# week7.net
KiCad netlist of a schematic drawn in EAGLE
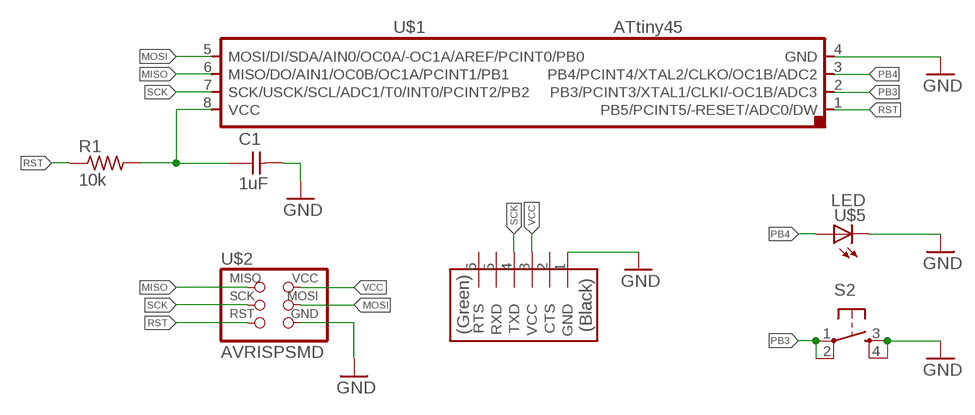
[diagram p0: schematic, sheet 1]

(export (version "E")
  (design (tool "Eeschema 10.0.6"))
  (components
    (comp (ref "C1")
      (value "1uF")
      (footprint "eagle-import:C1206FAB")
      (libsource (lib "eagle-import") (part "CAP-UNPOLARIZEDFAB"))
    )
    (comp (ref "R1")
      (value "10k")
      (footprint "eagle-import:R1206")
      (libsource (lib "eagle-import") (part "RES-US1206"))
    )
    (comp (ref "S2")
      (value "6MM_SWITCH6MM_SWITCH")
      (footprint "eagle-import:6MM_SWITCH")
      (libsource (lib "eagle-import") (part "6MM_SWITCH6MM_SWITCH"))
    )
    (comp (ref "U$1")
      (value "ATTINY45SI")
      (footprint "eagle-import:SOIC8")
      (libsource (lib "eagle-import") (part "ATTINY45SI"))
    )
    (comp (ref "U$2")
      (value "AVRISPSMD")
      (footprint "eagle-import:2X03SMD")
      (libsource (lib "eagle-import") (part "AVRISPSMD"))
    )
    (comp (ref "U$3")
      (value "FTDI-SMD-HEADER")
      (footprint "eagle-import:1X06SMD")
      (libsource (lib "eagle-import") (part "FTDI-SMD-HEADER"))
    )
    (comp (ref "U$5")
      (value "LED")
      (footprint "eagle-import:LED1206")
      (libsource (lib "eagle-import") (part "LED"))
    )
  )
  (nets
    (net (code "1") (name "GND") (class "Default")
      (node (ref "C1") (pin "2") (pinfunction "2_2") (pintype "passive"))
      (node (ref "S2") (pin "3") (pinfunction "S_3") (pintype "passive"))
      (node (ref "S2") (pin "4") (pinfunction "S1_4") (pintype "passive"))
      (node (ref "U$1") (pin "4") (pinfunction "GND_4") (pintype "bidirectional"))
      (node (ref "U$2") (pin "6") (pinfunction "GND_6") (pintype "passive"))
      (node (ref "U$3") (pin "1") (pinfunction "GND_1") (pintype "bidirectional"))
      (node (ref "U$5") (pin "2") (pinfunction "C_2") (pintype "passive"))
    )
    (net (code "2") (name "MISO") (class "Default")
      (node (ref "U$1") (pin "6") (pinfunction "MISO/DO/AIN1/OC0B/OC1A/PCINT1/PB1_6") (pintype "bidirectional"))
      (node (ref "U$2") (pin "1") (pinfunction "MISO_1") (pintype "passive"))
    )
    (net (code "3") (name "MOSI") (class "Default")
      (node (ref "U$1") (pin "5") (pinfunction "MOSI/DI/SDA/AIN0/OC0A/-OC1A/AREF/PCINT0/PB0_5") (pintype "bidirectional"))
      (node (ref "U$2") (pin "4") (pinfunction "MOSI_4") (pintype "passive"))
    )
    (net (code "4") (name "Net-(U$1-VCC)") (class "Default")
      (node (ref "C1") (pin "1") (pinfunction "1_1") (pintype "passive"))
      (node (ref "R1") (pin "2") (pinfunction "2_2") (pintype "passive"))
      (node (ref "U$1") (pin "8") (pinfunction "VCC_8") (pintype "bidirectional"))
    )
    (net (code "5") (name "PB3") (class "Default")
      (node (ref "S2") (pin "1") (pinfunction "P_1") (pintype "passive"))
      (node (ref "S2") (pin "2") (pinfunction "P1_2") (pintype "passive"))
      (node (ref "U$1") (pin "2") (pinfunction "PB3/PCINT3/XTAL1/CLKI/-OC1B/ADC3_2") (pintype "bidirectional"))
    )
    (net (code "6") (name "PB4") (class "Default")
      (node (ref "U$1") (pin "3") (pinfunction "PB4/PCINT4/XTAL2/CLKO/OC1B/ADC2_3") (pintype "bidirectional"))
      (node (ref "U$5") (pin "1") (pinfunction "A_1") (pintype "passive"))
    )
    (net (code "7") (name "RST") (class "Default")
      (node (ref "R1") (pin "1") (pinfunction "1_1") (pintype "passive"))
      (node (ref "U$1") (pin "1") (pinfunction "PB5/PCINT5/-RESET/ADC0/DW_1") (pintype "bidirectional"))
      (node (ref "U$2") (pin "5") (pinfunction "RST_5") (pintype "passive"))
    )
    (net (code "8") (name "SCK") (class "Default")
      (node (ref "U$1") (pin "7") (pinfunction "SCK/USCK/SCL/ADC1/T0/INT0/PCINT2/PB2_7") (pintype "bidirectional"))
      (node (ref "U$2") (pin "3") (pinfunction "SCK_3") (pintype "passive"))
      (node (ref "U$3") (pin "4") (pinfunction "TXD_4") (pintype "bidirectional"))
    )
    (net (code "9") (name "VCC") (class "Default")
      (node (ref "U$2") (pin "2") (pinfunction "VCC_2") (pintype "passive"))
      (node (ref "U$3") (pin "3") (pinfunction "VCC_3") (pintype "bidirectional"))
    )
    (net (code "10") (name "unconnected-(U$3-CTS-Pad2)") (class "Default")
      (node (ref "U$3") (pin "2") (pinfunction "CTS_2") (pintype "bidirectional"))
    )
    (net (code "11") (name "unconnected-(U$3-RTS-Pad6)") (class "Default")
      (node (ref "U$3") (pin "6") (pinfunction "RTS_6") (pintype "bidirectional"))
    )
    (net (code "12") (name "unconnected-(U$3-RXD-Pad5)") (class "Default")
      (node (ref "U$3") (pin "5") (pinfunction "RXD_5") (pintype "bidirectional"))
    )
  )
)
